# Sheet1.net
KiCad netlist of a schematic drawn in Altium Designer
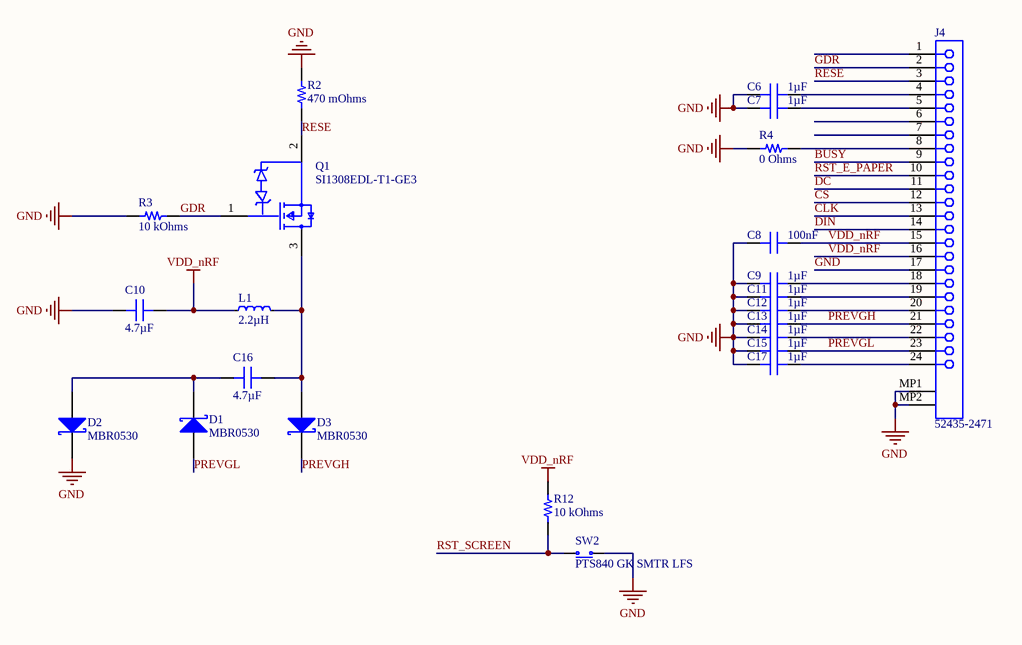
[diagram p0: Sheet1.SchDoc]

(export (version "E")
  (design (tool "Eeschema 10.0.6"))
  (components
    (comp (ref "C6")
      (value "1µF")
      (footprint "CAP 0603_1608")
      (description "CAP CER 1UF 4V X5R 0603")
      (fields (field (name "PART NUMBER") "C0603C105K7PAC7867") (field (name "MANUFACTURER") "KEMET"))
      (libsource (lib "Celestial Altium Library - altium_library") (part "Capacitor"))
    )
    (comp (ref "C7")
      (value "1µF")
      (footprint "CAP 0603_1608")
      (description "CAP CER 1UF 4V X5R 0603")
      (fields (field (name "PART NUMBER") "C0603C105K7PAC7867") (field (name "MANUFACTURER") "KEMET"))
      (libsource (lib "Celestial Altium Library - altium_library") (part "Capacitor"))
    )
    (comp (ref "C8")
      (value "100nF")
      (footprint "CAP 0603_1608")
      (description "CAP CER 100nF 4V X5R 0603")
      (fields (field (name "PART NUMBER") "C0603C105K7PAC7867") (field (name "MANUFACTURER") "KEMET"))
      (libsource (lib "Celestial Altium Library - altium_library") (part "Capacitor"))
    )
    (comp (ref "C9")
      (value "1µF")
      (footprint "CAP 0603_1608")
      (description "CAP CER 1UF 4V X5R 0603")
      (fields (field (name "PART NUMBER") "C0603C105K7PAC7867") (field (name "MANUFACTURER") "KEMET"))
      (libsource (lib "Celestial Altium Library - altium_library") (part "Capacitor"))
    )
    (comp (ref "C10")
      (value "4.7µF")
      (footprint "CAP 0603_1608")
      (description "CAP CER 4.7UF 10V X5R 0603")
      (fields (field (name "PART NUMBER") "LMK107BJ475KA-T") (field (name "MANUFACTURER") "Taiyo Yuden"))
      (libsource (lib "Celestial Altium Library - altium_library") (part "Capacitor"))
    )
    (comp (ref "C11")
      (value "1µF")
      (footprint "CAP 0603_1608")
      (description "CAP CER 1UF 4V X5R 0603")
      (fields (field (name "PART NUMBER") "C0603C105K7PAC7867") (field (name "MANUFACTURER") "KEMET"))
      (libsource (lib "Celestial Altium Library - altium_library") (part "Capacitor"))
    )
    (comp (ref "C12")
      (value "1µF")
      (footprint "CAP 0603_1608")
      (description "CAP CER 1UF 4V X5R 0603")
      (fields (field (name "PART NUMBER") "C0603C105K7PAC7867") (field (name "MANUFACTURER") "KEMET"))
      (libsource (lib "Celestial Altium Library - altium_library") (part "Capacitor"))
    )
    (comp (ref "C13")
      (value "1µF")
      (footprint "CAP 0603_1608")
      (description "CAP CER 1UF 4V X5R 0603")
      (fields (field (name "PART NUMBER") "C0603C105K7PAC7867") (field (name "MANUFACTURER") "KEMET"))
      (libsource (lib "Celestial Altium Library - altium_library") (part "Capacitor"))
    )
    (comp (ref "C14")
      (value "1µF")
      (footprint "CAP 0603_1608")
      (description "CAP CER 1UF 4V X5R 0603")
      (fields (field (name "PART NUMBER") "C0603C105K7PAC7867") (field (name "MANUFACTURER") "KEMET"))
      (libsource (lib "Celestial Altium Library - altium_library") (part "Capacitor"))
    )
    (comp (ref "C15")
      (value "1µF")
      (footprint "CAP 0603_1608")
      (description "CAP CER 1UF 4V X5R 0603")
      (fields (field (name "PART NUMBER") "C0603C105K7PAC7867") (field (name "MANUFACTURER") "KEMET"))
      (libsource (lib "Celestial Altium Library - altium_library") (part "Capacitor"))
    )
    (comp (ref "C16")
      (value "4.7µF")
      (footprint "CAP 0603_1608")
      (description "CAP CER 4.7UF 10V X5R 0603")
      (fields (field (name "PART NUMBER") "LMK107BJ475KA-T") (field (name "MANUFACTURER") "Taiyo Yuden"))
      (libsource (lib "Celestial Altium Library - altium_library") (part "Capacitor"))
    )
    (comp (ref "C17")
      (value "1µF")
      (footprint "CAP 0603_1608")
      (description "CAP CER 1UF 4V X5R 0603")
      (fields (field (name "PART NUMBER") "C0603C105K7PAC7867") (field (name "MANUFACTURER") "KEMET"))
      (libsource (lib "Celestial Altium Library - altium_library") (part "Capacitor"))
    )
    (comp (ref "D1")
      (value "MBR0530")
      (footprint "FAIR-SOD123-2_V")
      (description "Diode Schottky 30V 0.5A 2-Pin SOD-123 T/R")
      (fields (field (name "MANUFACTURER") "Fairchild"))
      (libsource (lib "Altium Content Vault") (part "DSKY-AK-2"))
    )
    (comp (ref "D2")
      (value "MBR0530")
      (footprint "FAIR-SOD123-2_V")
      (description "Diode Schottky 30V 0.5A 2-Pin SOD-123 T/R")
      (fields (field (name "MANUFACTURER") "Fairchild"))
      (libsource (lib "Altium Content Vault") (part "DSKY-AK-2"))
    )
    (comp (ref "D3")
      (value "MBR0530")
      (footprint "FAIR-SOD123-2_V")
      (description "Diode Schottky 30V 0.5A 2-Pin SOD-123 T/R")
      (fields (field (name "MANUFACTURER") "Fairchild"))
      (libsource (lib "Altium Content Vault") (part "DSKY-AK-2"))
    )
    (comp (ref "J4")
      (value "52435-2471")
      (footprint "MOLX-52435-2471")
      (fields (field (name "MANUFACTURER") "Molex"))
      (libsource (lib "Altium Content Vault") (part "MOLX-52435-2471"))
    )
    (comp (ref "L1")
      (value "2.2µH")
      (footprint "TY-NR3015")
      (description "Ferrite Inductor, Shielded, 1,5A, 72mOhm")
      (fields
        (field (name "PART NUMBER") "NR3015-2µ2-1.5A-72mOhm")
        (field (name "MANUFACTURER") "Taiyo Yuden")
        (field (name "PUBLISHER") "Nordic Semiconductor")
      )
      (libsource (lib "pca10056") (part "IND_1212"))
    )
    (comp (ref "Q1")
      (value "SI1308EDL-T1-GE3")
      (footprint "FP-S-03946-MFG")
      (description "MOSFET N-CH 30V 1.4A SC-70-3")
      (fields
        (field (name "OCTOPART") "https://octopart.com/si1308edl-t1-ge3-vishay-45284459")
        (field (name "MANUFACTURER") "Vishay")
      )
      (libsource (lib "Altium Content Vault") (part "b3bb3e825a9d846c0de22584db20962"))
    )
    (comp (ref "R2")
      (value "470 mOhms")
      (footprint "RES 0603_1608")
      (description "RES 0.47 OHM 1% 1/5W 0603")
      (fields (field (name "PART NUMBER") "RCWE0603R470FKEA") (field (name "MANUFACTURER") "Vishay Dale"))
      (libsource (lib "Celestial Altium Library - altium_library") (part "Resistor"))
    )
    (comp (ref "R3")
      (value "10 kOhms")
      (footprint "RES 0603_1608")
      (description "RES 10K OHM 0.1% 1/16W 0603")
      (fields
        (field (name "PART NUMBER") "RNCS0603BKE10K0")
        (field (name "MANUFACTURER") "Stackpole Electronics Inc")
      )
      (libsource (lib "Celestial Altium Library - altium_library") (part "Resistor"))
    )
    (comp (ref "R4")
      (value "0 Ohms")
      (footprint "RES 0603_1608")
      (description "RES SMD 0 OHM JUMPER 1/4W 0603")
      (fields (field (name "PART NUMBER") "CRCW06030000Z0EAHP") (field (name "MANUFACTURER") "Vishay Dale"))
      (libsource (lib "Celestial Altium Library - altium_library") (part "Resistor"))
    )
    (comp (ref "R12")
      (value "10 kOhms")
      (footprint "RES 0603_1608")
      (description "RES 10K OHM 0.1% 1/16W 0603")
      (fields
        (field (name "PART NUMBER") "RNCS0603BKE10K0")
        (field (name "MANUFACTURER") "Stackpole Electronics Inc")
      )
      (libsource (lib "Celestial Altium Library - altium_library") (part "Resistor"))
    )
    (comp (ref "SW2")
      (value "PTS840 GK SMTR LFS")
      (footprint "EVQP7A/J/B/K")
      (description "Microminiature SMT Switch, Side Actuated")
      (fields
        (field (name "MANUFACTURER") "C&K Components")
        (field (name "2ND SOURCE PART NUMBER") "611-PTS840GKSMTR")
        (field (name "PUBLISHER") "Nordic Semiconductor")
      )
      (libsource (lib "pca10059") (part "PTS840 GK SMTR LFS"))
    )
  )
  (nets
    (net (code "1") (name "/BUSY") (class "Default")
      (node (ref "J4") (pin "9") (pinfunction "9_9") (pintype "passive"))
    )
    (net (code "2") (name "/CLK") (class "Default")
      (node (ref "J4") (pin "13") (pinfunction "13_13") (pintype "passive"))
    )
    (net (code "3") (name "/CS") (class "Default")
      (node (ref "J4") (pin "12") (pinfunction "12_12") (pintype "passive"))
    )
    (net (code "4") (name "/DC") (class "Default")
      (node (ref "J4") (pin "11") (pinfunction "11_11") (pintype "passive"))
    )
    (net (code "5") (name "/DIN") (class "Default")
      (node (ref "J4") (pin "14") (pinfunction "14_14") (pintype "passive"))
    )
    (net (code "6") (name "/GDR") (class "Default")
      (node (ref "J4") (pin "2") (pinfunction "2_2") (pintype "passive"))
      (node (ref "Q1") (pin "1") (pinfunction "G_1") (pintype "passive"))
      (node (ref "R3") (pin "2") (pinfunction "2_2") (pintype "passive"))
    )
    (net (code "7") (name "/PREVGH") (class "Default")
      (node (ref "C13") (pin "2") (pinfunction "2_2") (pintype "passive"))
      (node (ref "D3") (pin "2") (pinfunction "K_2") (pintype "passive"))
      (node (ref "J4") (pin "21") (pinfunction "21_21") (pintype "passive"))
    )
    (net (code "8") (name "/PREVGL") (class "Default")
      (node (ref "C15") (pin "2") (pinfunction "2_2") (pintype "passive"))
      (node (ref "D1") (pin "1") (pinfunction "A_1") (pintype "passive"))
      (node (ref "J4") (pin "23") (pinfunction "23_23") (pintype "passive"))
    )
    (net (code "9") (name "/RESE") (class "Default")
      (node (ref "J4") (pin "3") (pinfunction "3_3") (pintype "passive"))
      (node (ref "Q1") (pin "2") (pinfunction "S_2") (pintype "passive"))
      (node (ref "R2") (pin "1") (pinfunction "1_1") (pintype "passive"))
    )
    (net (code "10") (name "/RST_E_PAPER") (class "Default")
      (node (ref "J4") (pin "10") (pinfunction "10_10") (pintype "passive"))
    )
    (net (code "11") (name "/RST_SCREEN") (class "Default")
      (node (ref "R12") (pin "2") (pinfunction "2_2") (pintype "passive"))
      (node (ref "SW2") (pin "1") (pinfunction "N.O_1") (pintype "passive"))
    )
    (net (code "12") (name "GND") (class "Default")
      (node (ref "C10") (pin "1") (pinfunction "1_1") (pintype "passive"))
      (node (ref "C11") (pin "1") (pinfunction "1_1") (pintype "passive"))
      (node (ref "C12") (pin "1") (pinfunction "1_1") (pintype "passive"))
      (node (ref "C13") (pin "1") (pinfunction "1_1") (pintype "passive"))
      (node (ref "C14") (pin "1") (pinfunction "1_1") (pintype "passive"))
      (node (ref "C15") (pin "1") (pinfunction "1_1") (pintype "passive"))
      (node (ref "C17") (pin "1") (pinfunction "1_1") (pintype "passive"))
      (node (ref "C6") (pin "1") (pinfunction "1_1") (pintype "passive"))
      (node (ref "C7") (pin "1") (pinfunction "1_1") (pintype "passive"))
      (node (ref "C8") (pin "1") (pinfunction "1_1") (pintype "passive"))
      (node (ref "C9") (pin "1") (pinfunction "1_1") (pintype "passive"))
      (node (ref "D2") (pin "2") (pinfunction "K_2") (pintype "passive"))
      (node (ref "J4") (pin "17") (pinfunction "17_17") (pintype "passive"))
      (node (ref "J4") (pin "MP1") (pinfunction "MP1_MP1") (pintype "passive"))
      (node (ref "J4") (pin "MP2") (pinfunction "MP2_MP2") (pintype "passive"))
      (node (ref "R2") (pin "2") (pinfunction "2_2") (pintype "passive"))
      (node (ref "R3") (pin "1") (pinfunction "1_1") (pintype "passive"))
      (node (ref "R4") (pin "1") (pinfunction "1_1") (pintype "passive"))
      (node (ref "SW2") (pin "2") (pinfunction "COM_2") (pintype "passive"))
    )
    (net (code "13") (name "Net-(C6-Pad2)") (class "Default")
      (node (ref "C6") (pin "2") (pinfunction "2_2") (pintype "passive"))
      (node (ref "J4") (pin "4") (pinfunction "4_4") (pintype "passive"))
    )
    (net (code "14") (name "Net-(C7-Pad2)") (class "Default")
      (node (ref "C7") (pin "2") (pinfunction "2_2") (pintype "passive"))
      (node (ref "J4") (pin "5") (pinfunction "5_5") (pintype "passive"))
    )
    (net (code "15") (name "Net-(C9-Pad2)") (class "Default")
      (node (ref "C9") (pin "2") (pinfunction "2_2") (pintype "passive"))
      (node (ref "J4") (pin "18") (pinfunction "18_18") (pintype "passive"))
    )
    (net (code "16") (name "Net-(C11-Pad2)") (class "Default")
      (node (ref "C11") (pin "2") (pinfunction "2_2") (pintype "passive"))
      (node (ref "J4") (pin "19") (pinfunction "19_19") (pintype "passive"))
    )
    (net (code "17") (name "Net-(C12-Pad2)") (class "Default")
      (node (ref "C12") (pin "2") (pinfunction "2_2") (pintype "passive"))
      (node (ref "J4") (pin "20") (pinfunction "20_20") (pintype "passive"))
    )
    (net (code "18") (name "Net-(C14-Pad2)") (class "Default")
      (node (ref "C14") (pin "2") (pinfunction "2_2") (pintype "passive"))
      (node (ref "J4") (pin "22") (pinfunction "22_22") (pintype "passive"))
    )
    (net (code "19") (name "Net-(C17-Pad2)") (class "Default")
      (node (ref "C17") (pin "2") (pinfunction "2_2") (pintype "passive"))
      (node (ref "J4") (pin "24") (pinfunction "24_24") (pintype "passive"))
    )
    (net (code "20") (name "Net-(D1-K)") (class "Default")
      (node (ref "C16") (pin "1") (pinfunction "1_1") (pintype "passive"))
      (node (ref "D1") (pin "2") (pinfunction "K_2") (pintype "passive"))
      (node (ref "D2") (pin "1") (pinfunction "A_1") (pintype "passive"))
    )
    (net (code "21") (name "Net-(D3-A)") (class "Default")
      (node (ref "C16") (pin "2") (pinfunction "2_2") (pintype "passive"))
      (node (ref "D3") (pin "1") (pinfunction "A_1") (pintype "passive"))
      (node (ref "L1") (pin "2") (pinfunction "2_2") (pintype "passive"))
      (node (ref "Q1") (pin "3") (pinfunction "D_3") (pintype "passive"))
    )
    (net (code "22") (name "Net-(J4-Pad8)") (class "Default")
      (node (ref "J4") (pin "8") (pinfunction "8_8") (pintype "passive"))
      (node (ref "R4") (pin "2") (pinfunction "2_2") (pintype "passive"))
    )
    (net (code "23") (name "VDD_nRF") (class "Default")
      (node (ref "C10") (pin "2") (pinfunction "2_2") (pintype "passive"))
      (node (ref "C8") (pin "2") (pinfunction "2_2") (pintype "passive"))
      (node (ref "J4") (pin "15") (pinfunction "15_15") (pintype "passive"))
      (node (ref "J4") (pin "16") (pinfunction "16_16") (pintype "passive"))
      (node (ref "L1") (pin "1") (pinfunction "1_1") (pintype "passive"))
      (node (ref "R12") (pin "1") (pinfunction "1_1") (pintype "passive"))
    )
    (net (code "24") (name "unconnected-(J4-Pad1)") (class "Default")
      (node (ref "J4") (pin "1") (pinfunction "1_1") (pintype "passive"))
    )
    (net (code "25") (name "unconnected-(J4-Pad6)") (class "Default")
      (node (ref "J4") (pin "6") (pinfunction "6_6") (pintype "passive"))
    )
    (net (code "26") (name "unconnected-(J4-Pad7)") (class "Default")
      (node (ref "J4") (pin "7") (pinfunction "7_7") (pintype "passive"))
    )
  )
)
